# Step_Down.net
KiCad netlist of a schematic drawn in Altium Designer
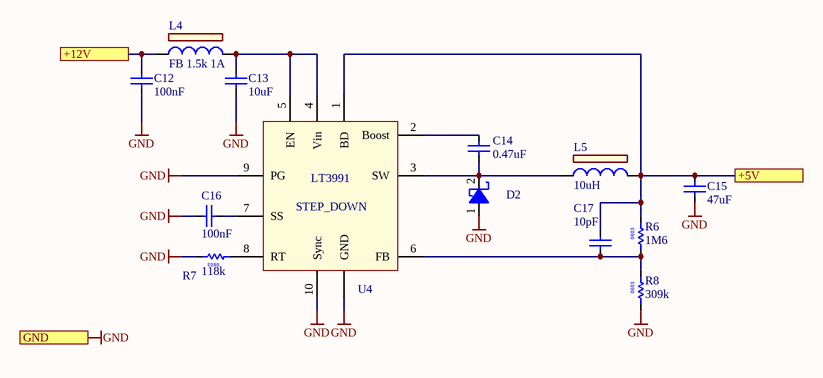
[diagram p0: Step_Down.SchDoc]

(export (version "E")
  (design (tool "Eeschema 10.0.6"))
  (components
    (comp (ref "C12")
      (value "100nF")
      (footprint "C0603V")
      (description "MLCC, 0.1uF 16V 10% X7R 0603")
      (fields (field (name "PART NUMBER") "C0000005") (field (name "VOLTAGE") "16"))
      (libsource (lib "KTU_DB") (part "C_SM"))
    )
    (comp (ref "C13")
      (value "10uF")
      (footprint "CAPC3216N")
      (description "MLCC, 10uF, 16V, 10%, 1206")
      (fields (field (name "PART NUMBER") "C0000006") (field (name "VOLTAGE") "16"))
      (libsource (lib "KTU_DB") (part "C_SM"))
    )
    (comp (ref "C14")
      (value "0.47uF")
      (footprint "CAPC2012N")
      (description "MLCC,0.47uF,50V, 0805,")
      (fields (field (name "PART NUMBER") "C0000094") (field (name "VOLTAGE") "50"))
      (libsource (lib "KTU_DB") (part "C_SM"))
    )
    (comp (ref "C15")
      (value "47uF")
      (footprint "CAPC2012N")
      (description "MLCC,47uF,50V, 0805,")
      (fields (field (name "PART NUMBER") "C0000094") (field (name "VOLTAGE") "50"))
      (libsource (lib "KTU_DB") (part "C_SM"))
    )
    (comp (ref "C16")
      (value "100nF")
      (footprint "C0603V")
      (description "MLCC, 0.1uF 16V 10% X7R 0603")
      (fields (field (name "PART NUMBER") "C0000005") (field (name "VOLTAGE") "16"))
      (libsource (lib "KTU_DB") (part "C_SM"))
    )
    (comp (ref "C17")
      (value "10pF")
      (footprint "CAPC1608N")
      (description "MLCC, 0603, NP0, 50V, 10PF")
      (fields (field (name "PART NUMBER") "C0000042") (field (name "VOLTAGE") "100"))
      (libsource (lib "KTU_DB") (part "C_SM"))
    )
    (comp (ref "D2")
      (value "PMEG3010ER")
      (footprint "SOD123")
      (description "1A, 30V")
      (fields (field (name "PART NUMBER") "D0000058") (field (name "MANUFACTURER") "NXP"))
      (libsource (lib "KTU_DB") (part "Diode_SCHOTTKY"))
    )
    (comp (ref "L4")
      (value "FB 1.5k 1A")
      (footprint "LL0805\\2P")
      (description "BEAD FERRITE, SMD 1500OHM, 0805")
      (fields (field (name "PART NUMBER") "L0000004") (field (name "MANUFACTURER") "Wurth Elektronik"))
      (libsource (lib "KTU_DB") (part "L_core"))
    )
    (comp (ref "L5")
      (value "10uH")
      (footprint "L1515")
      (description "INDUCTOR, SMD, 4X4MM, 10UH, 20%")
      (fields (field (name "PART NUMBER") "L0000071") (field (name "TOLERANCE") "20%"))
      (libsource (lib "KTU_DB") (part "L_core"))
    )
    (comp (ref "R6")
      (value "1M6")
      (footprint "RESC1608N")
      (description "1M6 5% 0603 1/10W")
      (fields (field (name "TOLERANCE") "±5%") (field (name "POWER") "1/10W"))
      (libsource (lib "KTU_DB") (part "R0603"))
    )
    (comp (ref "R7")
      (value "118k")
      (footprint "RESC1608X50N")
      (description "Res, 118K, 0603 (1608 metric), ±1%, 100mW, 75V")
      (fields (field (name "TOLERANCE") "±1%") (field (name "POWER") "100mW"))
      (libsource (lib "KTU_DB") (part "R0603"))
    )
    (comp (ref "R8")
      (value "309k")
      (footprint "RESC1608X50N")
      (description "Res, 309K, 0603 (1608 metric), ±1%, 100mW, 75V")
      (fields (field (name "TOLERANCE") "±1%") (field (name "POWER") "100mW"))
      (libsource (lib "KTU_DB") (part "R0603"))
    )
    (comp (ref "U4")
      (value "LT3991")
      (footprint "10-LEAD PLASTIC MSOP - duplicate")
      (description "55V, 1.2A Step-Down  Regulator with 2.8µA  Quiescent Current")
      (libsource (lib "D_klase") (part "LT3991"))
    )
  )
  (nets
    (net (code "1") (name "/+5V") (class "Default")
      (node (ref "C15") (pin "2") (pinfunction "2_2") (pintype "passive"))
      (node (ref "C17") (pin "2") (pinfunction "2_2") (pintype "passive"))
      (node (ref "L5") (pin "2") (pinfunction "2_2") (pintype "passive"))
      (node (ref "R6") (pin "2") (pinfunction "2_2") (pintype "passive"))
      (node (ref "U4") (pin "1") (pinfunction "BD_1") (pintype "passive"))
    )
    (net (code "2") (name "/+12V") (class "Default")
      (node (ref "C12") (pin "2") (pinfunction "2_2") (pintype "passive"))
      (node (ref "L4") (pin "1") (pinfunction "1_1") (pintype "passive"))
    )
    (net (code "3") (name "GND") (class "Default")
      (node (ref "C12") (pin "1") (pinfunction "1_1") (pintype "passive"))
      (node (ref "C13") (pin "2") (pinfunction "2_2") (pintype "passive"))
      (node (ref "C15") (pin "1") (pinfunction "1_1") (pintype "passive"))
      (node (ref "C16") (pin "1") (pinfunction "1_1") (pintype "passive"))
      (node (ref "D2") (pin "1") (pinfunction "ANODE_1") (pintype "passive"))
      (node (ref "R7") (pin "2") (pinfunction "2_2") (pintype "passive"))
      (node (ref "R8") (pin "1") (pinfunction "1_1") (pintype "passive"))
      (node (ref "U4") (pin "10") (pinfunction "Sync_10") (pintype "passive"))
      (node (ref "U4") (pin "9") (pinfunction "PG_9") (pintype "passive"))
      (node (ref "U4") (pin "GND") (pinfunction "GND_GND") (pintype "passive"))
    )
    (net (code "4") (name "Net-(D2-CATHODE)") (class "Default")
      (node (ref "C14") (pin "1") (pinfunction "1_1") (pintype "passive"))
      (node (ref "D2") (pin "2") (pinfunction "CATHODE_2") (pintype "passive"))
      (node (ref "L5") (pin "1") (pinfunction "1_1") (pintype "passive"))
      (node (ref "U4") (pin "3") (pinfunction "SW_3") (pintype "passive"))
    )
    (net (code "5") (name "Net-(U4-Boost)") (class "Default")
      (node (ref "C14") (pin "2") (pinfunction "2_2") (pintype "passive"))
      (node (ref "U4") (pin "2") (pinfunction "Boost_2") (pintype "passive"))
    )
    (net (code "6") (name "Net-(U4-EN)") (class "Default")
      (node (ref "C13") (pin "1") (pinfunction "1_1") (pintype "passive"))
      (node (ref "L4") (pin "2") (pinfunction "2_2") (pintype "passive"))
      (node (ref "U4") (pin "4") (pinfunction "Vin_4") (pintype "passive"))
      (node (ref "U4") (pin "5") (pinfunction "EN_5") (pintype "passive"))
    )
    (net (code "7") (name "Net-(U4-FB)") (class "Default")
      (node (ref "C17") (pin "1") (pinfunction "1_1") (pintype "passive"))
      (node (ref "R6") (pin "1") (pinfunction "1_1") (pintype "passive"))
      (node (ref "R8") (pin "2") (pinfunction "2_2") (pintype "passive"))
      (node (ref "U4") (pin "6") (pinfunction "FB_6") (pintype "passive"))
    )
    (net (code "8") (name "Net-(U4-RT)") (class "Default")
      (node (ref "R7") (pin "1") (pinfunction "1_1") (pintype "passive"))
      (node (ref "U4") (pin "8") (pinfunction "RT_8") (pintype "passive"))
    )
    (net (code "9") (name "Net-(U4-SS)") (class "Default")
      (node (ref "C16") (pin "2") (pinfunction "2_2") (pintype "passive"))
      (node (ref "U4") (pin "7") (pinfunction "SS_7") (pintype "passive"))
    )
  )
)
